# D1MSHO.net
KiCad netlist of a schematic drawn in EAGLE
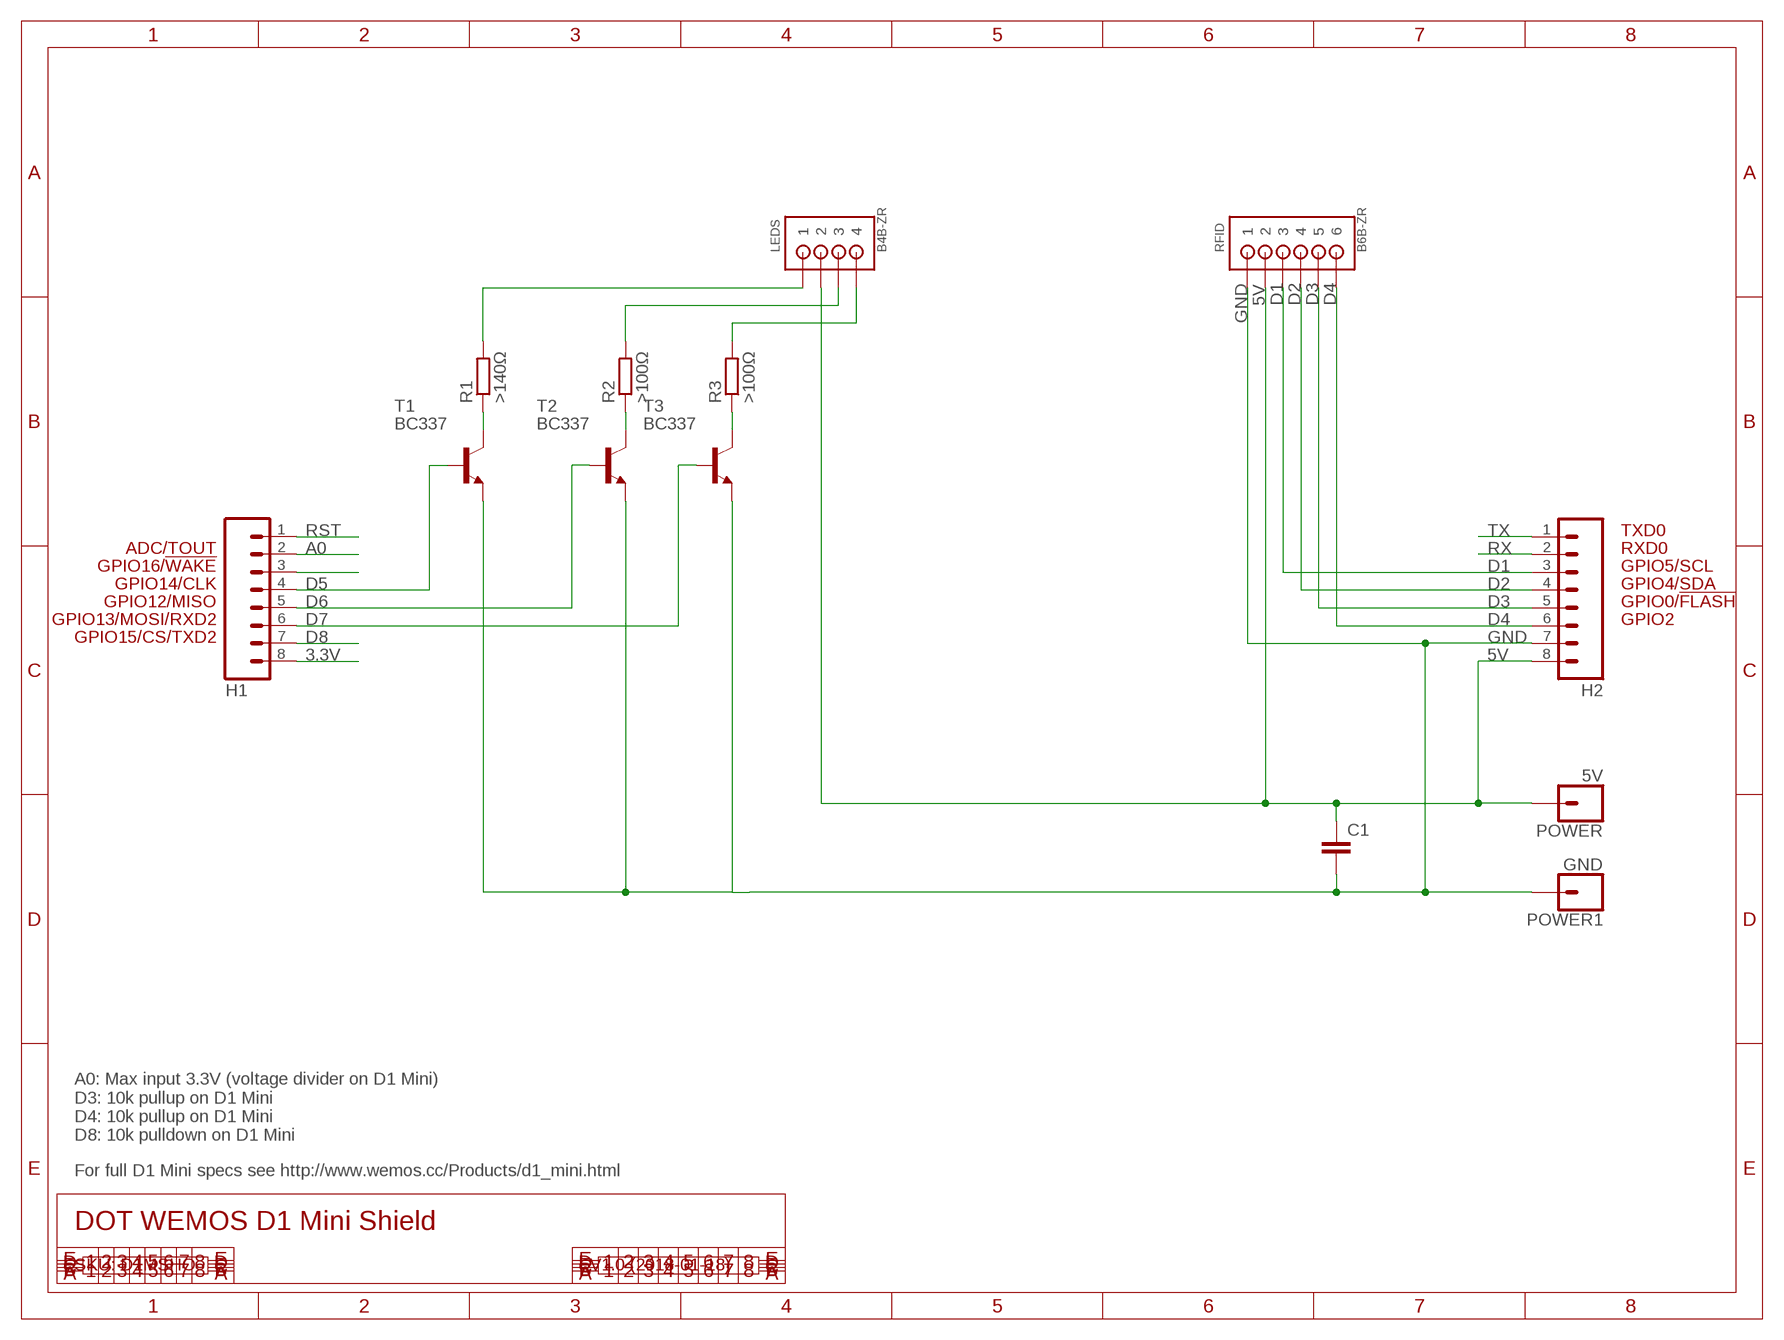
[diagram p0: schematic, sheet 1]

(export (version "E")
  (design (tool "Eeschema 10.0.6"))
  (components
    (comp (ref "C1")
      (value "C-EU050-025X075")
      (footprint "eagle-import:C050-025X075")
      (libsource (lib "eagle-import") (part "C-EU050-025X075"))
    )
    (comp (ref "H1")
      (value "M08")
      (footprint "eagle-import:1X08")
      (libsource (lib "eagle-import") (part "M08"))
    )
    (comp (ref "H2")
      (value "M08")
      (footprint "eagle-import:1X08")
      (libsource (lib "eagle-import") (part "M08"))
    )
    (comp (ref "LEDS")
      (value "B4B-ZR")
      (footprint "eagle-import:B4B-ZR")
      (libsource (lib "eagle-import") (part "B4B-ZR"))
    )
    (comp (ref "POWER")
      (value "5V")
      (footprint "eagle-import:1X01_OFFSET")
      (libsource (lib "eagle-import") (part "CONN_01OFFSET"))
    )
    (comp (ref "POWER1")
      (value "GND")
      (footprint "eagle-import:1X01_OFFSET")
      (libsource (lib "eagle-import") (part "CONN_01OFFSET"))
    )
    (comp (ref "R1")
      (value ">140Ω")
      (footprint "eagle-import:0204_5")
      (libsource (lib "eagle-import") (part "R-EU_0204/5"))
    )
    (comp (ref "R2")
      (value ">100Ω")
      (footprint "eagle-import:0204_5")
      (libsource (lib "eagle-import") (part "R-EU_0204/5"))
    )
    (comp (ref "R3")
      (value ">100Ω")
      (footprint "eagle-import:0204_5")
      (libsource (lib "eagle-import") (part "R-EU_0204/5"))
    )
    (comp (ref "RFID")
      (value "B6B-ZR")
      (footprint "eagle-import:B6B-ZR")
      (libsource (lib "eagle-import") (part "B6B-ZR"))
    )
    (comp (ref "T1")
      (value "BC337")
      (footprint "eagle-import:TO92")
      (libsource (lib "eagle-import") (part "BC337"))
    )
    (comp (ref "T2")
      (value "BC337")
      (footprint "eagle-import:TO92")
      (libsource (lib "eagle-import") (part "BC337"))
    )
    (comp (ref "T3")
      (value "BC337")
      (footprint "eagle-import:TO92")
      (libsource (lib "eagle-import") (part "BC337"))
    )
  )
  (nets
    (net (code "1") (name "/3.3V") (class "Default")
      (node (ref "H1") (pin "8") (pinfunction "8_8") (pintype "passive"))
    )
    (net (code "2") (name "/5V") (class "Default")
      (node (ref "C1") (pin "1") (pinfunction "1_1") (pintype "passive"))
      (node (ref "H2") (pin "8") (pinfunction "8_8") (pintype "passive"))
      (node (ref "LEDS") (pin "2") (pinfunction "2_2") (pintype "bidirectional"))
      (node (ref "POWER") (pin "1") (pinfunction "1_1") (pintype "passive"))
      (node (ref "RFID") (pin "2") (pinfunction "2_2") (pintype "bidirectional"))
    )
    (net (code "3") (name "/A0") (class "Default")
      (node (ref "H1") (pin "2") (pinfunction "2_2") (pintype "passive"))
    )
    (net (code "4") (name "/D1") (class "Default")
      (node (ref "H2") (pin "3") (pinfunction "3_3") (pintype "passive"))
      (node (ref "RFID") (pin "3") (pinfunction "3_3") (pintype "bidirectional"))
    )
    (net (code "5") (name "/D2") (class "Default")
      (node (ref "H2") (pin "4") (pinfunction "4_4") (pintype "passive"))
      (node (ref "RFID") (pin "4") (pinfunction "4_4") (pintype "bidirectional"))
    )
    (net (code "6") (name "/D3") (class "Default")
      (node (ref "H2") (pin "5") (pinfunction "5_5") (pintype "passive"))
      (node (ref "RFID") (pin "5") (pinfunction "5_5") (pintype "bidirectional"))
    )
    (net (code "7") (name "/D4") (class "Default")
      (node (ref "H2") (pin "6") (pinfunction "6_6") (pintype "passive"))
      (node (ref "RFID") (pin "6") (pinfunction "6_6") (pintype "bidirectional"))
    )
    (net (code "8") (name "/D5") (class "Default")
      (node (ref "H1") (pin "4") (pinfunction "4_4") (pintype "passive"))
      (node (ref "T1") (pin "2") (pinfunction "B_2") (pintype "passive"))
    )
    (net (code "9") (name "/D6") (class "Default")
      (node (ref "H1") (pin "5") (pinfunction "5_5") (pintype "passive"))
      (node (ref "T2") (pin "2") (pinfunction "B_2") (pintype "passive"))
    )
    (net (code "10") (name "/D7") (class "Default")
      (node (ref "H1") (pin "6") (pinfunction "6_6") (pintype "passive"))
      (node (ref "T3") (pin "2") (pinfunction "B_2") (pintype "passive"))
    )
    (net (code "11") (name "/D8") (class "Default")
      (node (ref "H1") (pin "7") (pinfunction "7_7") (pintype "passive"))
    )
    (net (code "12") (name "/GND") (class "Default")
      (node (ref "C1") (pin "2") (pinfunction "2_2") (pintype "passive"))
      (node (ref "H2") (pin "7") (pinfunction "7_7") (pintype "passive"))
      (node (ref "POWER1") (pin "1") (pinfunction "1_1") (pintype "passive"))
      (node (ref "RFID") (pin "1") (pinfunction "1_1") (pintype "bidirectional"))
      (node (ref "T1") (pin "1") (pinfunction "E_1") (pintype "passive"))
      (node (ref "T2") (pin "1") (pinfunction "E_1") (pintype "passive"))
      (node (ref "T3") (pin "1") (pinfunction "E_1") (pintype "passive"))
    )
    (net (code "13") (name "/RST") (class "Default")
      (node (ref "H1") (pin "1") (pinfunction "1_1") (pintype "passive"))
    )
    (net (code "14") (name "/RX") (class "Default")
      (node (ref "H2") (pin "2") (pinfunction "2_2") (pintype "passive"))
    )
    (net (code "15") (name "/TX") (class "Default")
      (node (ref "H2") (pin "1") (pinfunction "1_1") (pintype "passive"))
    )
    (net (code "16") (name "Net-(LEDS-Pad1)") (class "Default")
      (node (ref "LEDS") (pin "1") (pinfunction "1_1") (pintype "bidirectional"))
      (node (ref "R1") (pin "2") (pinfunction "2_2") (pintype "passive"))
    )
    (net (code "17") (name "Net-(LEDS-Pad3)") (class "Default")
      (node (ref "LEDS") (pin "3") (pinfunction "3_3") (pintype "bidirectional"))
      (node (ref "R2") (pin "2") (pinfunction "2_2") (pintype "passive"))
    )
    (net (code "18") (name "Net-(LEDS-Pad4)") (class "Default")
      (node (ref "LEDS") (pin "4") (pinfunction "4_4") (pintype "bidirectional"))
      (node (ref "R3") (pin "2") (pinfunction "2_2") (pintype "passive"))
    )
    (net (code "19") (name "Net-(T1-C)") (class "Default")
      (node (ref "R1") (pin "1") (pinfunction "1_1") (pintype "passive"))
      (node (ref "T1") (pin "3") (pinfunction "C_3") (pintype "passive"))
    )
    (net (code "20") (name "Net-(T2-C)") (class "Default")
      (node (ref "R2") (pin "1") (pinfunction "1_1") (pintype "passive"))
      (node (ref "T2") (pin "3") (pinfunction "C_3") (pintype "passive"))
    )
    (net (code "21") (name "Net-(T3-C)") (class "Default")
      (node (ref "R3") (pin "1") (pinfunction "1_1") (pintype "passive"))
      (node (ref "T3") (pin "3") (pinfunction "C_3") (pintype "passive"))
    )
    (net (code "22") (name "unconnected-(H1-Pad3)") (class "Default")
      (node (ref "H1") (pin "3") (pinfunction "3_3") (pintype "passive"))
    )
  )
)
